# TermWylPomp1_cpu.net
KiCad netlist of a schematic drawn in Altium Designer
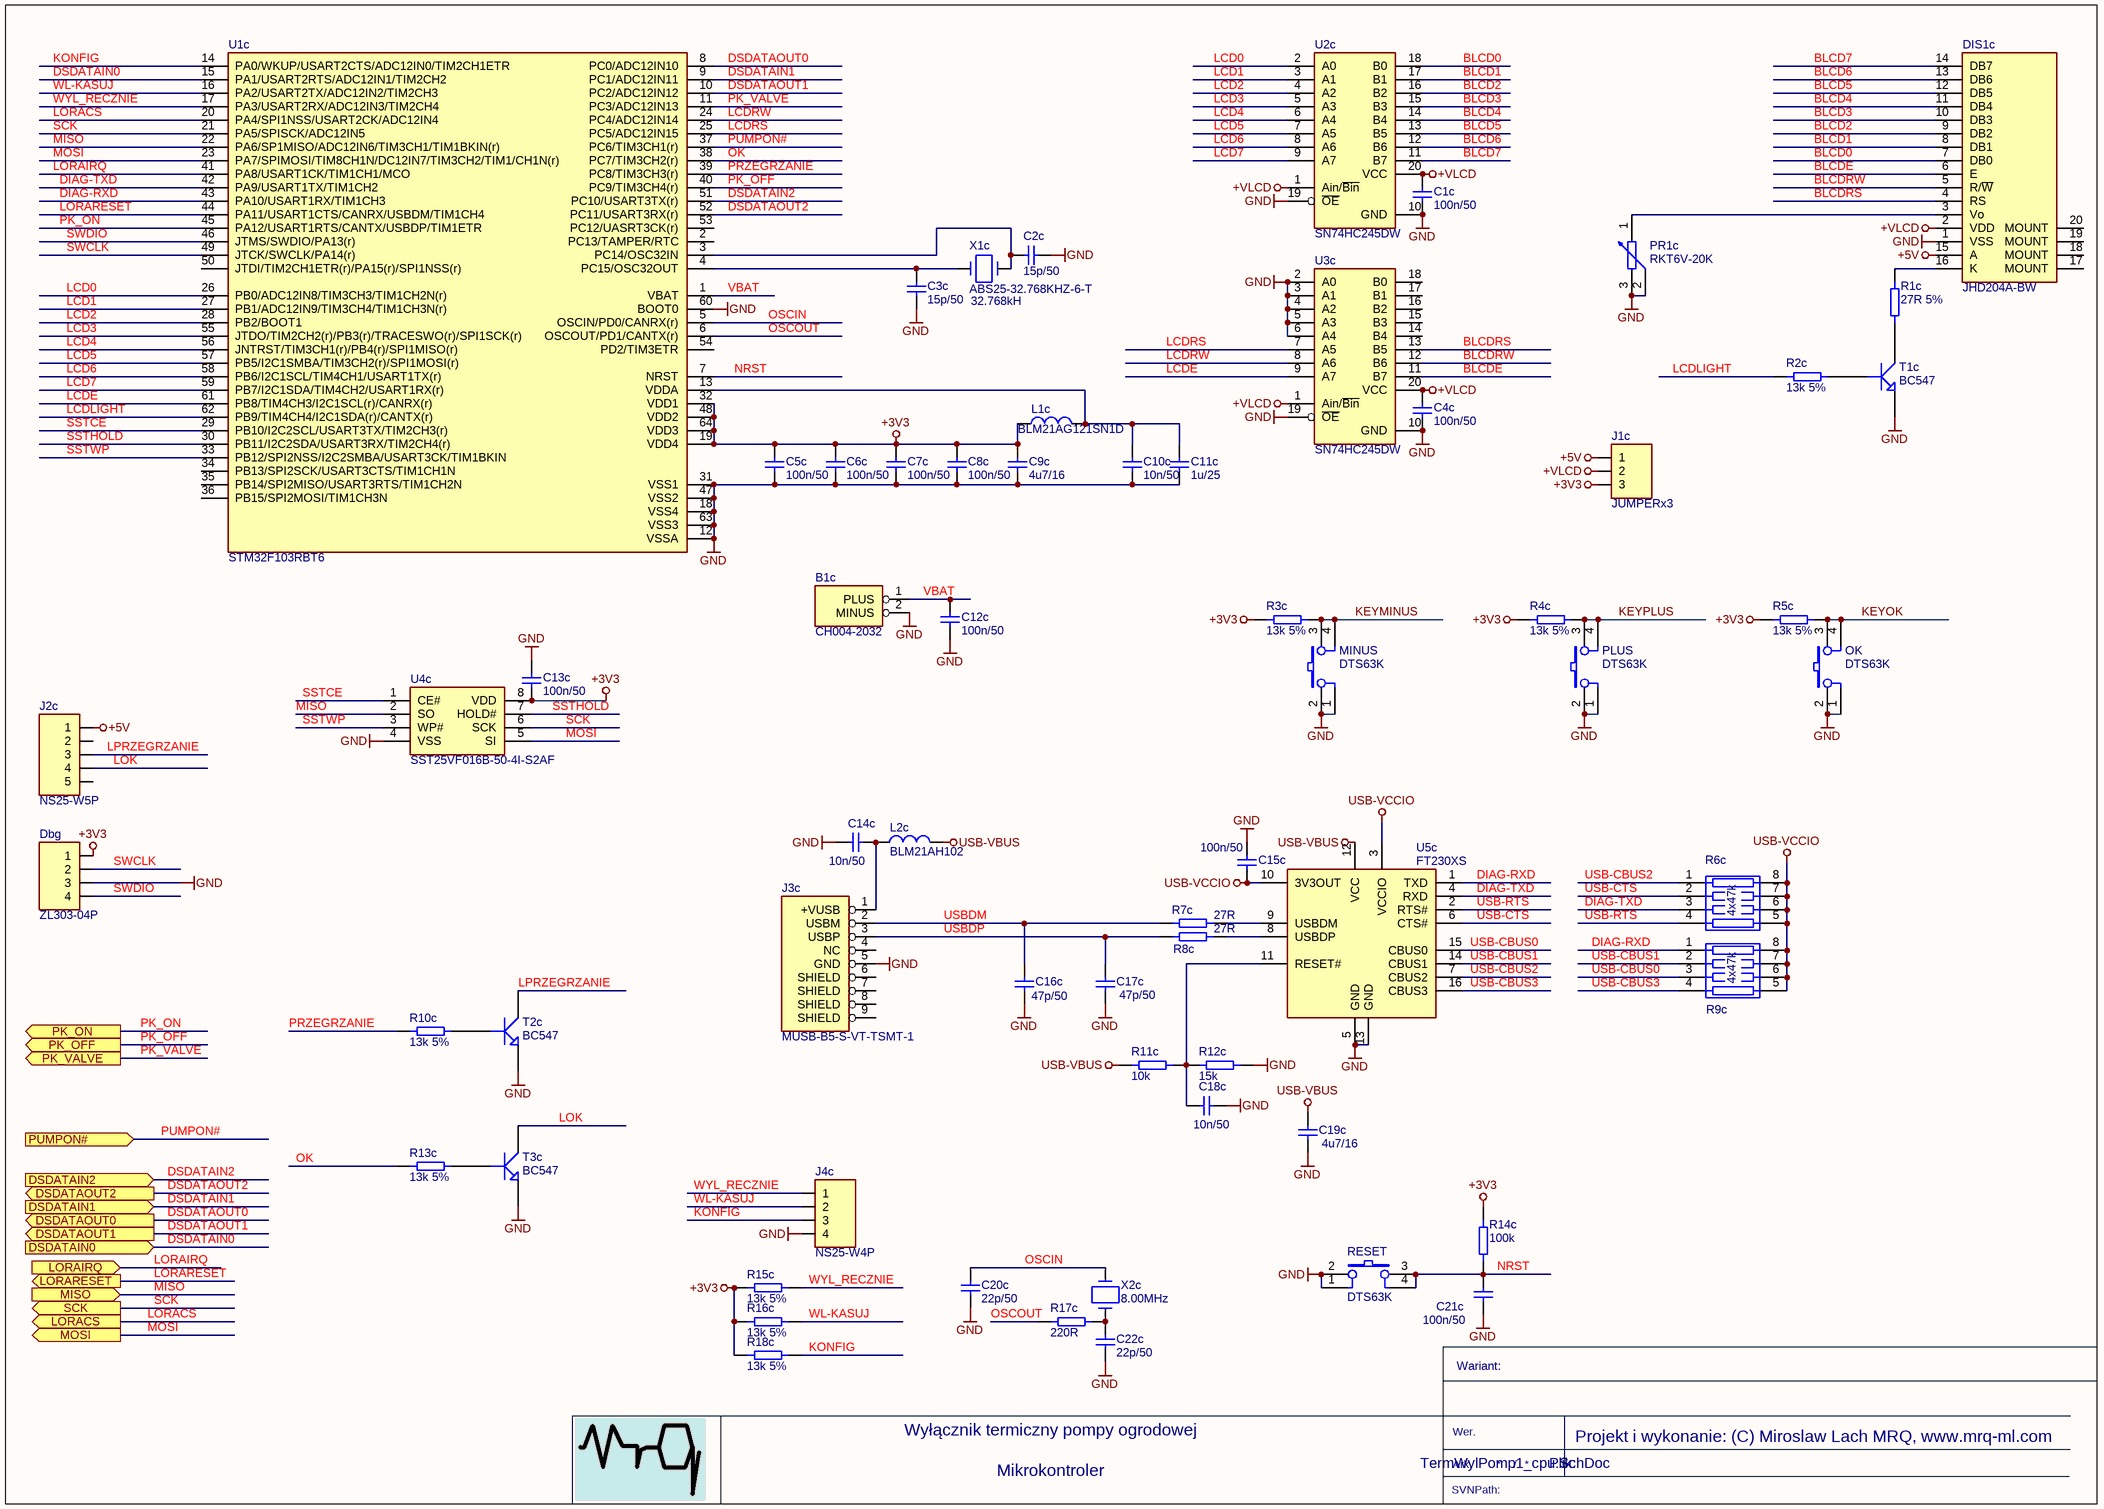
[diagram p0: TermWylPomp1_cpu.SchDoc]

(export (version "E")
  (design (tool "Eeschema 10.0.6"))
  (components
    (comp (ref "B1c")
      (value "CH004-2032")
      (footprint "CH004-2032")
      (libsource (lib "PartsMySQL") (part "BATTSOCK"))
    )
    (comp (ref "C1c") (value "100n/50") (footprint "0805") (libsource (lib "PartsMySQL") (part "C")))
    (comp (ref "C2c") (value "15p/50") (footprint "0603-IPC") (libsource (lib "PartsMySQL") (part "C")))
    (comp (ref "C3c") (value "15p/50") (footprint "0603-IPC") (libsource (lib "PartsMySQL") (part "C")))
    (comp (ref "C4c") (value "100n/50") (footprint "0805") (libsource (lib "PartsMySQL") (part "C")))
    (comp (ref "C5c") (value "100n/50") (footprint "0805") (libsource (lib "PartsMySQL") (part "C")))
    (comp (ref "C6c") (value "100n/50") (footprint "0805") (libsource (lib "PartsMySQL") (part "C")))
    (comp (ref "C7c") (value "100n/50") (footprint "0805") (libsource (lib "PartsMySQL") (part "C")))
    (comp (ref "C8c") (value "100n/50") (footprint "0805") (libsource (lib "PartsMySQL") (part "C")))
    (comp (ref "C9c") (value "4u7/16") (footprint "0805") (libsource (lib "PartsMySQL") (part "C")))
    (comp (ref "C10c") (value "10n/50") (footprint "0805") (libsource (lib "PartsMySQL") (part "C")))
    (comp (ref "C11c") (value "1u/25") (footprint "0805") (libsource (lib "PartsMySQL") (part "C")))
    (comp (ref "C12c") (value "100n/50") (footprint "0805") (libsource (lib "PartsMySQL") (part "C")))
    (comp (ref "C13c") (value "100n/50") (footprint "0805") (libsource (lib "PartsMySQL") (part "C")))
    (comp (ref "C14c") (value "10n/50") (footprint "0805") (libsource (lib "PartsMySQL") (part "C")))
    (comp (ref "C15c") (value "100n/50") (footprint "0805") (libsource (lib "PartsMySQL") (part "C")))
    (comp (ref "C16c") (value "47p/50") (footprint "0603-IPC") (libsource (lib "PartsMySQL") (part "C")))
    (comp (ref "C17c") (value "47p/50") (footprint "0603-IPC") (libsource (lib "PartsMySQL") (part "C")))
    (comp (ref "C18c") (value "10n/50") (footprint "0805") (libsource (lib "PartsMySQL") (part "C")))
    (comp (ref "C19c") (value "4u7/16") (footprint "0805") (libsource (lib "PartsMySQL") (part "C")))
    (comp (ref "C20c") (value "22p/50") (footprint "0805") (libsource (lib "PartsMySQL") (part "C")))
    (comp (ref "C21c") (value "100n/50") (footprint "0805") (libsource (lib "PartsMySQL") (part "C")))
    (comp (ref "C22c") (value "22p/50") (footprint "0805") (libsource (lib "PartsMySQL") (part "C")))
    (comp (ref "Dbg") (value "ZL303-04P") (footprint "PLMS4S") (libsource (lib "") (part "HEADER4_1")))
    (comp (ref "DIS1c")
      (value "JHD204A-BW")
      (footprint "JHD204A")
      (libsource (lib "PartsMySQL") (part "LCM2002LED"))
    )
    (comp (ref "J1c")
      (value "JUMPERx3")
      (footprint "3SIP100")
      (libsource (lib "PartsMySQL") (part "HEADER3"))
    )
    (comp (ref "J2c") (value "NS25-W5P") (footprint "WF05S") (libsource (lib "PartsMySQL") (part "HEADER5")))
    (comp (ref "J3c")
      (value "MUSB-B5-S-VT-TSMT-1")
      (footprint "MUSB-B5-S-VT-TSMT1")
      (libsource (lib "PartsMySQL") (part "MUSB-B5-S-VT-TSMT1"))
    )
    (comp (ref "J4c") (value "NS25-W4P") (footprint "WF04S") (libsource (lib "PartsMySQL") (part "HEADER4")))
    (comp (ref "L1c")
      (value "BLM21AG121SN1D")
      (footprint "0805")
      (libsource (lib "PartsMySQL") (part "INDUCTOR"))
    )
    (comp (ref "L2c")
      (value "BLM21AH102")
      (footprint "0805")
      (libsource (lib "PartsMySQL") (part "INDUCTOR"))
    )
    (comp (ref "MINUS") (value "DTS63K") (footprint "DTS63K") (libsource (lib "PartsMySQL") (part "SWPUSH")))
    (comp (ref "OK") (value "DTS63K") (footprint "DTS63K") (libsource (lib "PartsMySQL") (part "SWPUSH")))
    (comp (ref "PLUS") (value "DTS63K") (footprint "DTS63K") (libsource (lib "PartsMySQL") (part "SWPUSH")))
    (comp (ref "PR1c") (value "RKT6V-20K") (footprint "RKT6V") (libsource (lib "PartsMySQL") (part "RV2")))
    (comp (ref "R1c") (value "27R 5%") (footprint "R402510") (libsource (lib "PartsMySQL") (part "R")))
    (comp (ref "R2c") (value "13k 5%") (footprint "R402510") (libsource (lib "PartsMySQL") (part "R")))
    (comp (ref "R3c") (value "13k 5%") (footprint "R402510") (libsource (lib "PartsMySQL") (part "R")))
    (comp (ref "R4c") (value "13k 5%") (footprint "R402510") (libsource (lib "PartsMySQL") (part "R")))
    (comp (ref "R5c") (value "13k 5%") (footprint "R402510") (libsource (lib "PartsMySQL") (part "R")))
    (comp (ref "R6c") (value "4x47k") (footprint "1206RP") (libsource (lib "PartsMySQL") (part "DR1206")))
    (comp (ref "R7c") (value "27R") (footprint "0603R") (libsource (lib "PartsMySQL") (part "R")))
    (comp (ref "R8c") (value "27R") (footprint "0603R") (libsource (lib "PartsMySQL") (part "R")))
    (comp (ref "R9c") (value "4x47k") (footprint "1206RP") (libsource (lib "PartsMySQL") (part "DR1206")))
    (comp (ref "R10c") (value "13k 5%") (footprint "R402510") (libsource (lib "PartsMySQL") (part "R")))
    (comp (ref "R11c") (value "10k") (footprint "0805R") (libsource (lib "PartsMySQL") (part "R")))
    (comp (ref "R12c") (value "15k") (footprint "0805R") (libsource (lib "PartsMySQL") (part "R")))
    (comp (ref "R13c") (value "13k 5%") (footprint "R402510") (libsource (lib "PartsMySQL") (part "R")))
    (comp (ref "R14c") (value "100k") (footprint "R402510") (libsource (lib "PartsMySQL") (part "R")))
    (comp (ref "R15c") (value "13k 5%") (footprint "R402510") (libsource (lib "PartsMySQL") (part "R")))
    (comp (ref "R16c") (value "13k 5%") (footprint "R402510") (libsource (lib "PartsMySQL") (part "R")))
    (comp (ref "R17c") (value "220R") (footprint "0805R") (libsource (lib "PartsMySQL") (part "R")))
    (comp (ref "R18c") (value "13k 5%") (footprint "R402510") (libsource (lib "PartsMySQL") (part "R")))
    (comp (ref "RESET") (value "DTS63K") (footprint "DTS63K") (libsource (lib "PartsMySQL") (part "SWPUSH")))
    (comp (ref "T1c") (value "BC547") (footprint "CE35V4") (libsource (lib "PartsMySQL") (part "NPN_CE35V4")))
    (comp (ref "T2c") (value "BC547") (footprint "CE35V4") (libsource (lib "PartsMySQL") (part "NPN_CE35V4")))
    (comp (ref "T3c") (value "BC547") (footprint "CE35V4") (libsource (lib "PartsMySQL") (part "NPN_CE35V4")))
    (comp (ref "U1c")
      (value "STM32F103RBT6")
      (footprint "MS-026BCD")
      (libsource (lib "PartsMySQL") (part "STM32F103RBT6"))
    )
    (comp (ref "U2c")
      (value "SN74HC245DW")
      (footprint "20SOIC300")
      (libsource (lib "PartsMySQL") (part "74245"))
    )
    (comp (ref "U3c")
      (value "SN74HC245DW")
      (footprint "20SOIC300")
      (libsource (lib "PartsMySQL") (part "74245"))
    )
    (comp (ref "U4c")
      (value "SST25VF016B-50-4I-S2AF")
      (footprint "8SOIC200")
      (libsource (lib "PartsMySQL") (part "SST25VF016B"))
    )
    (comp (ref "U5c")
      (value "FT230XS")
      (footprint "MO-137AB")
      (libsource (lib "PartsMySQL") (part "FT230XS"))
    )
    (comp (ref "X1c")
      (value "ABS25-32.768KHZ-6-T")
      (footprint "ABS25CRYSTAL")
      (fields (field (name "FREQ") "32.768kH"))
      (libsource (lib "PartsMySQL") (part "CRYSTAL"))
    )
    (comp (ref "X2c") (value "8.00MHz") (footprint "HC49SMP") (libsource (lib "PartsMySQL") (part "CRYSTAL")))
  )
  (nets
    (net (code "1") (name "+3V3") (class "Default")
      (node (ref "C13c") (pin "1") (pinfunction "1_1") (pintype "passive"))
      (node (ref "C5c") (pin "1") (pinfunction "1_1") (pintype "passive"))
      (node (ref "C6c") (pin "1") (pinfunction "1_1") (pintype "passive"))
      (node (ref "C7c") (pin "1") (pinfunction "1_1") (pintype "passive"))
      (node (ref "C8c") (pin "1") (pinfunction "1_1") (pintype "passive"))
      (node (ref "C9c") (pin "1") (pinfunction "1_1") (pintype "passive"))
      (node (ref "Dbg") (pin "1") (pinfunction "1_1") (pintype "passive"))
      (node (ref "J1c") (pin "3") (pinfunction "3_3") (pintype "passive"))
      (node (ref "L1c") (pin "1") (pinfunction "1_1") (pintype "passive"))
      (node (ref "R14c") (pin "1") (pinfunction "1_1") (pintype "passive"))
      (node (ref "R15c") (pin "1") (pinfunction "1_1") (pintype "passive"))
      (node (ref "R16c") (pin "2") (pinfunction "2_2") (pintype "passive"))
      (node (ref "R18c") (pin "1") (pinfunction "1_1") (pintype "passive"))
      (node (ref "R3c") (pin "1") (pinfunction "1_1") (pintype "passive"))
      (node (ref "R4c") (pin "1") (pinfunction "1_1") (pintype "passive"))
      (node (ref "R5c") (pin "1") (pinfunction "1_1") (pintype "passive"))
      (node (ref "U1c") (pin "19") (pinfunction "VDD4_19") (pintype "passive"))
      (node (ref "U1c") (pin "32") (pinfunction "VDD1_32") (pintype "passive"))
      (node (ref "U1c") (pin "48") (pinfunction "VDD2_48") (pintype "passive"))
      (node (ref "U1c") (pin "64") (pinfunction "VDD3_64") (pintype "passive"))
      (node (ref "U4c") (pin "8") (pinfunction "VDD_8") (pintype "passive"))
    )
    (net (code "2") (name "+5V") (class "Default")
      (node (ref "DIS1c") (pin "15") (pinfunction "A_15") (pintype "passive"))
      (node (ref "J1c") (pin "1") (pinfunction "1_1") (pintype "passive"))
      (node (ref "J2c") (pin "1") (pinfunction "1_1") (pintype "passive"))
    )
    (net (code "3") (name "+VLCD") (class "Default")
      (node (ref "C1c") (pin "1") (pinfunction "1_1") (pintype "passive"))
      (node (ref "C4c") (pin "1") (pinfunction "1_1") (pintype "passive"))
      (node (ref "DIS1c") (pin "2") (pinfunction "VDD_2") (pintype "passive"))
      (node (ref "J1c") (pin "2") (pinfunction "2_2") (pintype "passive"))
      (node (ref "U2c") (pin "1") (pinfunction "Ain/~{Bin}_1") (pintype "passive"))
      (node (ref "U2c") (pin "20") (pinfunction "VCC_20") (pintype "power_in"))
      (node (ref "U3c") (pin "1") (pinfunction "Ain/~{Bin}_1") (pintype "passive"))
      (node (ref "U3c") (pin "20") (pinfunction "VCC_20") (pintype "power_in"))
    )
    (net (code "4") (name "/BLCD0") (class "Default")
      (node (ref "DIS1c") (pin "7") (pinfunction "DB0_7") (pintype "passive"))
      (node (ref "U2c") (pin "18") (pinfunction "B0_18") (pintype "passive"))
    )
    (net (code "5") (name "/BLCD1") (class "Default")
      (node (ref "DIS1c") (pin "8") (pinfunction "DB1_8") (pintype "passive"))
      (node (ref "U2c") (pin "17") (pinfunction "B1_17") (pintype "passive"))
    )
    (net (code "6") (name "/BLCD2") (class "Default")
      (node (ref "DIS1c") (pin "9") (pinfunction "DB2_9") (pintype "passive"))
      (node (ref "U2c") (pin "16") (pinfunction "B2_16") (pintype "passive"))
    )
    (net (code "7") (name "/BLCD3") (class "Default")
      (node (ref "DIS1c") (pin "10") (pinfunction "DB3_10") (pintype "passive"))
      (node (ref "U2c") (pin "15") (pinfunction "B3_15") (pintype "passive"))
    )
    (net (code "8") (name "/BLCD4") (class "Default")
      (node (ref "DIS1c") (pin "11") (pinfunction "DB4_11") (pintype "passive"))
      (node (ref "U2c") (pin "14") (pinfunction "B4_14") (pintype "passive"))
    )
    (net (code "9") (name "/BLCD5") (class "Default")
      (node (ref "DIS1c") (pin "12") (pinfunction "DB5_12") (pintype "passive"))
      (node (ref "U2c") (pin "13") (pinfunction "B5_13") (pintype "passive"))
    )
    (net (code "10") (name "/BLCD6") (class "Default")
      (node (ref "DIS1c") (pin "13") (pinfunction "DB6_13") (pintype "passive"))
      (node (ref "U2c") (pin "12") (pinfunction "B6_12") (pintype "passive"))
    )
    (net (code "11") (name "/BLCD7") (class "Default")
      (node (ref "DIS1c") (pin "14") (pinfunction "DB7_14") (pintype "passive"))
      (node (ref "U2c") (pin "11") (pinfunction "B7_11") (pintype "passive"))
    )
    (net (code "12") (name "/BLCDE") (class "Default")
      (node (ref "DIS1c") (pin "6") (pinfunction "E_6") (pintype "passive"))
      (node (ref "U3c") (pin "11") (pinfunction "B7_11") (pintype "passive"))
    )
    (net (code "13") (name "/BLCDRS") (class "Default")
      (node (ref "DIS1c") (pin "4") (pinfunction "RS_4") (pintype "passive"))
      (node (ref "U3c") (pin "13") (pinfunction "B5_13") (pintype "passive"))
    )
    (net (code "14") (name "/BLCDRW") (class "Default")
      (node (ref "DIS1c") (pin "5") (pinfunction "R/~{W}_5") (pintype "passive"))
      (node (ref "U3c") (pin "12") (pinfunction "B6_12") (pintype "passive"))
    )
    (net (code "15") (name "/DIAG-RXD") (class "Default")
      (node (ref "R9c") (pin "1") (pinfunction "R1_1") (pintype "passive"))
      (node (ref "U1c") (pin "43") (pinfunction "PA10/USART1RX/TIM1CH3_43") (pintype "passive"))
      (node (ref "U5c") (pin "1") (pinfunction "TXD_1") (pintype "passive"))
    )
    (net (code "16") (name "/DIAG-TXD") (class "Default")
      (node (ref "R6c") (pin "3") (pinfunction "R3_3") (pintype "passive"))
      (node (ref "U1c") (pin "42") (pinfunction "PA9/USART1TX/TIM1CH2_42") (pintype "passive"))
      (node (ref "U5c") (pin "4") (pinfunction "RXD_4") (pintype "passive"))
    )
    (net (code "17") (name "/DSDATAIN0") (class "Default")
      (node (ref "U1c") (pin "15") (pinfunction "PA1/USART2RTS/ADC12IN1/TIM2CH2_15") (pintype "passive"))
    )
    (net (code "18") (name "/DSDATAIN1") (class "Default")
      (node (ref "U1c") (pin "9") (pinfunction "PC1/ADC12IN11_9") (pintype "passive"))
    )
    (net (code "19") (name "/DSDATAIN2") (class "Default")
      (node (ref "U1c") (pin "51") (pinfunction "PC10/USART3TX(r)_51") (pintype "passive"))
    )
    (net (code "20") (name "/DSDATAOUT0") (class "Default")
      (node (ref "U1c") (pin "8") (pinfunction "PC0/ADC12IN10_8") (pintype "passive"))
    )
    (net (code "21") (name "/DSDATAOUT1") (class "Default")
      (node (ref "U1c") (pin "10") (pinfunction "PC2/ADC12IN12_10") (pintype "passive"))
    )
    (net (code "22") (name "/DSDATAOUT2") (class "Default")
      (node (ref "U1c") (pin "52") (pinfunction "PC11/USART3RX(r)_52") (pintype "passive"))
    )
    (net (code "23") (name "/KEYMINUS") (class "Default")
      (node (ref "MINUS") (pin "3") (pinfunction "3_3") (pintype "passive"))
      (node (ref "MINUS") (pin "4") (pinfunction "4_4") (pintype "passive"))
      (node (ref "R3c") (pin "2") (pinfunction "2_2") (pintype "passive"))
    )
    (net (code "24") (name "/KEYOK") (class "Default")
      (node (ref "OK") (pin "3") (pinfunction "3_3") (pintype "passive"))
      (node (ref "OK") (pin "4") (pinfunction "4_4") (pintype "passive"))
      (node (ref "R5c") (pin "2") (pinfunction "2_2") (pintype "passive"))
    )
    (net (code "25") (name "/KEYPLUS") (class "Default")
      (node (ref "PLUS") (pin "3") (pinfunction "3_3") (pintype "passive"))
      (node (ref "PLUS") (pin "4") (pinfunction "4_4") (pintype "passive"))
      (node (ref "R4c") (pin "2") (pinfunction "2_2") (pintype "passive"))
    )
    (net (code "26") (name "/KONFIG") (class "Default")
      (node (ref "J4c") (pin "3") (pinfunction "3_3") (pintype "passive"))
      (node (ref "R18c") (pin "2") (pinfunction "2_2") (pintype "passive"))
      (node (ref "U1c") (pin "14") (pinfunction "PA0/WKUP/USART2CTS/ADC12IN0/TIM2CH1ETR_14") (pintype "passive"))
    )
    (net (code "27") (name "/LCD0") (class "Default")
      (node (ref "U1c") (pin "26") (pinfunction "PB0/ADC12IN8/TIM3CH3/TIM1CH2N(r)_26") (pintype "passive"))
      (node (ref "U2c") (pin "2") (pinfunction "A0_2") (pintype "passive"))
    )
    (net (code "28") (name "/LCD1") (class "Default")
      (node (ref "U1c") (pin "27") (pinfunction "PB1/ADC12IN9/TIM3CH4/TIM1CH3N(r)_27") (pintype "passive"))
      (node (ref "U2c") (pin "3") (pinfunction "A1_3") (pintype "passive"))
    )
    (net (code "29") (name "/LCD2") (class "Default")
      (node (ref "U1c") (pin "28") (pinfunction "PB2/BOOT1_28") (pintype "passive"))
      (node (ref "U2c") (pin "4") (pinfunction "A2_4") (pintype "passive"))
    )
    (net (code "30") (name "/LCD3") (class "Default")
      (node (ref "U1c") (pin "55") (pinfunction "JTDO/TIM2CH2(r)/PB3(r)/TRACESWO(r)/SPI1SCK(r)_55") (pintype "passive"))
      (node (ref "U2c") (pin "5") (pinfunction "A3_5") (pintype "passive"))
    )
    (net (code "31") (name "/LCD4") (class "Default")
      (node (ref "U1c") (pin "56") (pinfunction "JNTRST/TIM3CH1(r)/PB4(r)/SPI1MISO(r)_56") (pintype "passive"))
      (node (ref "U2c") (pin "6") (pinfunction "A4_6") (pintype "passive"))
    )
    (net (code "32") (name "/LCD5") (class "Default")
      (node (ref "U1c") (pin "57") (pinfunction "PB5/I2C1SMBA/TIM3CH2(r)/SPI1MOSI(r)_57") (pintype "passive"))
      (node (ref "U2c") (pin "7") (pinfunction "A5_7") (pintype "passive"))
    )
    (net (code "33") (name "/LCD6") (class "Default")
      (node (ref "U1c") (pin "58") (pinfunction "PB6/I2C1SCL/TIM4CH1/USART1TX(r)_58") (pintype "passive"))
      (node (ref "U2c") (pin "8") (pinfunction "A6_8") (pintype "passive"))
    )
    (net (code "34") (name "/LCD7") (class "Default")
      (node (ref "U1c") (pin "59") (pinfunction "PB7/I2C1SDA/TIM4CH2/USART1RX(r)_59") (pintype "passive"))
      (node (ref "U2c") (pin "9") (pinfunction "A7_9") (pintype "passive"))
    )
    (net (code "35") (name "/LCDE") (class "Default")
      (node (ref "U1c") (pin "61") (pinfunction "PB8/TIM4CH3/I2C1SCL(r)/CANRX(r)_61") (pintype "passive"))
      (node (ref "U3c") (pin "9") (pinfunction "A7_9") (pintype "passive"))
    )
    (net (code "36") (name "/LCDLIGHT") (class "Default")
      (node (ref "R2c") (pin "1") (pinfunction "1_1") (pintype "passive"))
      (node (ref "U1c") (pin "62") (pinfunction "PB9/TIM4CH4/I2C1SDA(r)/CANTX(r)_62") (pintype "passive"))
    )
    (net (code "37") (name "/LCDRS") (class "Default")
      (node (ref "U1c") (pin "25") (pinfunction "PC5/ADC12IN15_25") (pintype "passive"))
      (node (ref "U3c") (pin "7") (pinfunction "A5_7") (pintype "passive"))
    )
    (net (code "38") (name "/LCDRW") (class "Default")
      (node (ref "U1c") (pin "24") (pinfunction "PC4/ADC12IN14_24") (pintype "passive"))
      (node (ref "U3c") (pin "8") (pinfunction "A6_8") (pintype "passive"))
    )
    (net (code "39") (name "/LOK") (class "Default")
      (node (ref "J2c") (pin "4") (pinfunction "4_4") (pintype "passive"))
      (node (ref "T3c") (pin "COLL") (pinfunction "COLL_COLL") (pintype "passive"))
    )
    (net (code "40") (name "/LORACS") (class "Default")
      (node (ref "U1c") (pin "20") (pinfunction "PA4/SPI1NSS/USART2CK/ADC12IN4_20") (pintype "passive"))
    )
    (net (code "41") (name "/LORAIRQ") (class "Default")
      (node (ref "U1c") (pin "41") (pinfunction "PA8/USART1CK/TIM1CH1/MCO_41") (pintype "passive"))
    )
    (net (code "42") (name "/LORARESET") (class "Default")
      (node (ref "U1c") (pin "44") (pinfunction "PA11/USART1CTS/CANRX/USBDM/TIM1CH4_44") (pintype "passive"))
    )
    (net (code "43") (name "/LPRZEGRZANIE") (class "Default")
      (node (ref "J2c") (pin "3") (pinfunction "3_3") (pintype "passive"))
      (node (ref "T2c") (pin "COLL") (pinfunction "COLL_COLL") (pintype "passive"))
    )
    (net (code "44") (name "/MISO") (class "Default")
      (node (ref "U1c") (pin "22") (pinfunction "PA6/SP1MISO/ADC12IN6/TIM3CH1/TIM1BKIN(r)_22") (pintype "passive"))
      (node (ref "U4c") (pin "2") (pinfunction "SO_2") (pintype "passive"))
    )
    (net (code "45") (name "/MOSI") (class "Default")
      (node (ref "U1c") (pin "23") (pinfunction "PA7/SPIMOSI/TIM8CH1N/DC12IN7/TIM3CH2/TIM1/CH1N(r)_23") (pintype "passive"))
      (node (ref "U4c") (pin "5") (pinfunction "SI_5") (pintype "passive"))
    )
    (net (code "46") (name "/NRST") (class "Default")
      (node (ref "C21c") (pin "1") (pinfunction "1_1") (pintype "passive"))
      (node (ref "R14c") (pin "2") (pinfunction "2_2") (pintype "passive"))
      (node (ref "RESET") (pin "3") (pinfunction "3_3") (pintype "passive"))
      (node (ref "RESET") (pin "4") (pinfunction "4_4") (pintype "passive"))
      (node (ref "U1c") (pin "7") (pinfunction "NRST_7") (pintype "passive"))
    )
    (net (code "47") (name "/OK") (class "Default")
      (node (ref "R13c") (pin "1") (pinfunction "1_1") (pintype "passive"))
      (node (ref "U1c") (pin "38") (pinfunction "PC7/TIM3CH2(r)_38") (pintype "passive"))
    )
    (net (code "48") (name "/OSCIN") (class "Default")
      (node (ref "C20c") (pin "2") (pinfunction "2_2") (pintype "passive"))
      (node (ref "U1c") (pin "5") (pinfunction "OSCIN/PD0/CANRX(r)_5") (pintype "passive"))
      (node (ref "X2c") (pin "2") (pinfunction "2_2") (pintype "passive"))
    )
    (net (code "49") (name "/OSCOUT") (class "Default")
      (node (ref "R17c") (pin "1") (pinfunction "1_1") (pintype "passive"))
      (node (ref "U1c") (pin "6") (pinfunction "OSCOUT/PD1/CANTX(r)_6") (pintype "passive"))
    )
    (net (code "50") (name "/PK_OFF") (class "Default")
      (node (ref "U1c") (pin "40") (pinfunction "PC9/TIM3CH4(r)_40") (pintype "passive"))
    )
    (net (code "51") (name "/PK_ON") (class "Default")
      (node (ref "U1c") (pin "45") (pinfunction "PA12/USART1RTS/CANTX/USBDP/TIM1ETR_45") (pintype "passive"))
    )
    (net (code "52") (name "/PK_VALVE") (class "Default")
      (node (ref "U1c") (pin "11") (pinfunction "PC3/ADC12IN13_11") (pintype "passive"))
    )
    (net (code "53") (name "/PRZEGRZANIE") (class "Default")
      (node (ref "R10c") (pin "1") (pinfunction "1_1") (pintype "passive"))
      (node (ref "U1c") (pin "39") (pinfunction "PC8/TIM3CH3(r)_39") (pintype "passive"))
    )
    (net (code "54") (name "/PUMPON#") (class "Default")
      (node (ref "U1c") (pin "37") (pinfunction "PC6/TIM3CH1(r)_37") (pintype "passive"))
    )
    (net (code "55") (name "/SCK") (class "Default")
      (node (ref "U1c") (pin "21") (pinfunction "PA5/SPISCK/ADC12IN5_21") (pintype "passive"))
      (node (ref "U4c") (pin "6") (pinfunction "SCK_6") (pintype "passive"))
    )
    (net (code "56") (name "/SSTCE") (class "Default")
      (node (ref "U1c") (pin "29") (pinfunction "PB10/I2C2SCL/USART3TX/TIM2CH3(r)_29") (pintype "passive"))
      (node (ref "U4c") (pin "1") (pinfunction "CE#_1") (pintype "passive"))
    )
    (net (code "57") (name "/SSTHOLD") (class "Default")
      (node (ref "U1c") (pin "30") (pinfunction "PB11/I2C2SDA/USART3RX/TIM2CH4(r)_30") (pintype "passive"))
      (node (ref "U4c") (pin "7") (pinfunction "HOLD#_7") (pintype "passive"))
    )
    (net (code "58") (name "/SSTWP") (class "Default")
      (node (ref "U1c") (pin "33") (pinfunction "PB12/SPI2NSS/I2C2SMBA/USART3CK/TIM1BKIN_33") (pintype "passive"))
      (node (ref "U4c") (pin "3") (pinfunction "WP#_3") (pintype "passive"))
    )
    (net (code "59") (name "/SWCLK") (class "Default")
      (node (ref "Dbg") (pin "2") (pinfunction "2_2") (pintype "passive"))
      (node (ref "U1c") (pin "49") (pinfunction "JTCK/SWCLK/PA14(r)_49") (pintype "passive"))
    )
    (net (code "60") (name "/SWDIO") (class "Default")
      (node (ref "Dbg") (pin "4") (pinfunction "4_4") (pintype "passive"))
      (node (ref "U1c") (pin "46") (pinfunction "JTMS/SWDIO/PA13(r)_46") (pintype "passive"))
    )
    (net (code "61") (name "/USB-CBUS0") (class "Default")
      (node (ref "R9c") (pin "3") (pinfunction "R3_3") (pintype "passive"))
      (node (ref "U5c") (pin "15") (pinfunction "CBUS0_15") (pintype "passive"))
    )
    (net (code "62") (name "/USB-CBUS1") (class "Default")
      (node (ref "R9c") (pin "2") (pinfunction "R2_2") (pintype "passive"))
      (node (ref "U5c") (pin "14") (pinfunction "CBUS1_14") (pintype "passive"))
    )
    (net (code "63") (name "/USB-CBUS2") (class "Default")
      (node (ref "R6c") (pin "1") (pinfunction "R1_1") (pintype "passive"))
      (node (ref "U5c") (pin "7") (pinfunction "CBUS2_7") (pintype "passive"))
    )
    (net (code "64") (name "/USB-CBUS3") (class "Default")
      (node (ref "R9c") (pin "4") (pinfunction "R4_4") (pintype "passive"))
      (node (ref "U5c") (pin "16") (pinfunction "CBUS3_16") (pintype "passive"))
    )
    (net (code "65") (name "/USB-CTS") (class "Default")
      (node (ref "R6c") (pin "2") (pinfunction "R2_2") (pintype "passive"))
      (node (ref "U5c") (pin "6") (pinfunction "CTS#_6") (pintype "passive"))
    )
    (net (code "66") (name "/USB-RTS") (class "Default")
      (node (ref "R6c") (pin "4") (pinfunction "R4_4") (pintype "passive"))
      (node (ref "U5c") (pin "2") (pinfunction "RTS#_2") (pintype "passive"))
    )
    (net (code "67") (name "/USBDM") (class "Default")
      (node (ref "C16c") (pin "1") (pinfunction "1_1") (pintype "passive"))
      (node (ref "J3c") (pin "2") (pinfunction "USBM_2") (pintype "passive"))
      (node (ref "R7c") (pin "1") (pinfunction "1_1") (pintype "passive"))
    )
    (net (code "68") (name "/USBDP") (class "Default")
      (node (ref "C17c") (pin "1") (pinfunction "1_1") (pintype "passive"))
      (node (ref "J3c") (pin "3") (pinfunction "USBP_3") (pintype "passive"))
      (node (ref "R8c") (pin "1") (pinfunction "1_1") (pintype "passive"))
    )
    (net (code "69") (name "/VBAT") (class "Default")
      (node (ref "B1c") (pin "1") (pinfunction "PLUS_1") (pintype "passive"))
      (node (ref "C12c") (pin "1") (pinfunction "1_1") (pintype "passive"))
      (node (ref "U1c") (pin "1") (pinfunction "VBAT_1") (pintype "passive"))
    )
    (net (code "70") (name "/WL-KASUJ") (class "Default")
      (node (ref "J4c") (pin "2") (pinfunction "2_2") (pintype "passive"))
      (node (ref "R16c") (pin "1") (pinfunction "1_1") (pintype "passive"))
      (node (ref "U1c") (pin "16") (pinfunction "PA2/USART2TX/ADC12IN2/TIM2CH3_16") (pintype "passive"))
    )
    (net (code "71") (name "/WYL_RECZNIE") (class "Default")
      (node (ref "J4c") (pin "1") (pinfunction "1_1") (pintype "passive"))
      (node (ref "R15c") (pin "2") (pinfunction "2_2") (pintype "passive"))
      (node (ref "U1c") (pin "17") (pinfunction "PA3/USART2RX/ADC12IN3/TIM2CH4_17") (pintype "passive"))
    )
    (net (code "72") (name "GND") (class "Default")
      (node (ref "B1c") (pin "2") (pinfunction "MINUS_2") (pintype "passive"))
      (node (ref "C10c") (pin "2") (pinfunction "2_2") (pintype "passive"))
      (node (ref "C11c") (pin "2") (pinfunction "2_2") (pintype "passive"))
      (node (ref "C12c") (pin "2") (pinfunction "2_2") (pintype "passive"))
      (node (ref "C13c") (pin "2") (pinfunction "2_2") (pintype "passive"))
      (node (ref "C14c") (pin "1") (pinfunction "1_1") (pintype "passive"))
      (node (ref "C15c") (pin "1") (pinfunction "1_1") (pintype "passive"))
      (node (ref "C16c") (pin "2") (pinfunction "2_2") (pintype "passive"))
      (node (ref "C17c") (pin "2") (pinfunction "2_2") (pintype "passive"))
      (node (ref "C18c") (pin "1") (pinfunction "1_1") (pintype "passive"))
      (node (ref "C19c") (pin "2") (pinfunction "2_2") (pintype "passive"))
      (node (ref "C1c") (pin "2") (pinfunction "2_2") (pintype "passive"))
      (node (ref "C20c") (pin "1") (pinfunction "1_1") (pintype "passive"))
      (node (ref "C21c") (pin "2") (pinfunction "2_2") (pintype "passive"))
      (node (ref "C22c") (pin "1") (pinfunction "1_1") (pintype "passive"))
      (node (ref "C2c") (pin "1") (pinfunction "1_1") (pintype "passive"))
      (node (ref "C3c") (pin "1") (pinfunction "1_1") (pintype "passive"))
      (node (ref "C4c") (pin "2") (pinfunction "2_2") (pintype "passive"))
      (node (ref "C5c") (pin "2") (pinfunction "2_2") (pintype "passive"))
      (node (ref "C6c") (pin "2") (pinfunction "2_2") (pintype "passive"))
      (node (ref "C7c") (pin "2") (pinfunction "2_2") (pintype "passive"))
      (node (ref "C8c") (pin "2") (pinfunction "2_2") (pintype "passive"))
      (node (ref "C9c") (pin "2") (pinfunction "2_2") (pintype "passive"))
      (node (ref "DIS1c") (pin "1") (pinfunction "VSS_1") (pintype "passive"))
      (node (ref "Dbg") (pin "3") (pinfunction "3_3") (pintype "passive"))
      (node (ref "J3c") (pin "5") (pinfunction "GND_5") (pintype "passive"))
      (node (ref "J4c") (pin "4") (pinfunction "4_4") (pintype "passive"))
      (node (ref "MINUS") (pin "1") (pinfunction "1_1") (pintype "passive"))
      (node (ref "MINUS") (pin "2") (pinfunction "2_2") (pintype "passive"))
      (node (ref "OK") (pin "1") (pinfunction "1_1") (pintype "passive"))
      (node (ref "OK") (pin "2") (pinfunction "2_2") (pintype "passive"))
      (node (ref "PLUS") (pin "1") (pinfunction "1_1") (pintype "passive"))
      (node (ref "PLUS") (pin "2") (pinfunction "2_2") (pintype "passive"))
      (node (ref "PR1c") (pin "2") (pinfunction "2_2") (pintype "passive"))
      (node (ref "PR1c") (pin "3") (pinfunction "3_3") (pintype "passive"))
      (node (ref "R12c") (pin "2") (pinfunction "2_2") (pintype "passive"))
      (node (ref "RESET") (pin "1") (pinfunction "1_1") (pintype "passive"))
      (node (ref "RESET") (pin "2") (pinfunction "2_2") (pintype "passive"))
      (node (ref "T1c") (pin "EMIT") (pinfunction "EMIT_EMIT") (pintype "passive"))
      (node (ref "T2c") (pin "EMIT") (pinfunction "EMIT_EMIT") (pintype "passive"))
      (node (ref "T3c") (pin "EMIT") (pinfunction "EMIT_EMIT") (pintype "passive"))
      (node (ref "U1c") (pin "12") (pinfunction "VSSA_12") (pintype "passive"))
      (node (ref "U1c") (pin "18") (pinfunction "VSS4_18") (pintype "passive"))
      (node (ref "U1c") (pin "31") (pinfunction "VSS1_31") (pintype "passive"))
      (node (ref "U1c") (pin "47") (pinfunction "VSS2_47") (pintype "passive"))
      (node (ref "U1c") (pin "60") (pinfunction "BOOT0_60") (pintype "passive"))
      (node (ref "U1c") (pin "63") (pinfunction "VSS3_63") (pintype "passive"))
      (node (ref "U2c") (pin "10") (pinfunction "GND_10") (pintype "power_in"))
      (node (ref "U2c") (pin "19") (pinfunction "~{OE}_19") (pintype "passive"))
      (node (ref "U3c") (pin "10") (pinfunction "GND_10") (pintype "power_in"))
      (node (ref "U3c") (pin "19") (pinfunction "~{OE}_19") (pintype "passive"))
      (node (ref "U3c") (pin "2") (pinfunction "A0_2") (pintype "passive"))
      (node (ref "U3c") (pin "3") (pinfunction "A1_3") (pintype "passive"))
      (node (ref "U3c") (pin "4") (pinfunction "A2_4") (pintype "passive"))
      (node (ref "U3c") (pin "5") (pinfunction "A3_5") (pintype "passive"))
      (node (ref "U3c") (pin "6") (pinfunction "A4_6") (pintype "passive"))
      (node (ref "U4c") (pin "4") (pinfunction "VSS_4") (pintype "passive"))
      (node (ref "U5c") (pin "13") (pinfunction "GND_13") (pintype "passive"))
      (node (ref "U5c") (pin "5") (pinfunction "GND_5") (pintype "passive"))
    )
    (net (code "73") (name "Net-(C22c-Pad2)") (class "Default")
      (node (ref "C22c") (pin "2") (pinfunction "2_2") (pintype "passive"))
      (node (ref "R17c") (pin "2") (pinfunction "2_2") (pintype "passive"))
      (node (ref "X2c") (pin "1") (pinfunction "1_1") (pintype "passive"))
    )
    (net (code "74") (name "Net-(DIS1c-K)") (class "Default")
      (node (ref "DIS1c") (pin "16") (pinfunction "K_16") (pintype "passive"))
      (node (ref "R1c") (pin "1") (pinfunction "1_1") (pintype "passive"))
    )
    (net (code "75") (name "Net-(DIS1c-Vo)") (class "Default")
      (node (ref "DIS1c") (pin "3") (pinfunction "Vo_3") (pintype "passive"))
      (node (ref "PR1c") (pin "1") (pinfunction "1_1") (pintype "passive"))
    )
    (net (code "76") (name "Net-(J3c-+VUSB)") (class "Default")
      (node (ref "C14c") (pin "2") (pinfunction "2_2") (pintype "passive"))
      (node (ref "J3c") (pin "1") (pinfunction "+VUSB_1") (pintype "passive"))
      (node (ref "L2c") (pin "1") (pinfunction "1_1") (pintype "passive"))
    )
    (net (code "77") (name "Net-(R1c-Pad2)") (class "Default")
      (node (ref "R1c") (pin "2") (pinfunction "2_2") (pintype "passive"))
      (node (ref "T1c") (pin "COLL") (pinfunction "COLL_COLL") (pintype "passive"))
    )
    (net (code "78") (name "Net-(R2c-Pad2)") (class "Default")
      (node (ref "R2c") (pin "2") (pinfunction "2_2") (pintype "passive"))
      (node (ref "T1c") (pin "BASE") (pinfunction "BASE_BASE") (pintype "passive"))
    )
    (net (code "79") (name "Net-(R10c-Pad2)") (class "Default")
      (node (ref "R10c") (pin "2") (pinfunction "2_2") (pintype "passive"))
      (node (ref "T2c") (pin "BASE") (pinfunction "BASE_BASE") (pintype "passive"))
    )
    (net (code "80") (name "Net-(R13c-Pad2)") (class "Default")
      (node (ref "R13c") (pin "2") (pinfunction "2_2") (pintype "passive"))
      (node (ref "T3c") (pin "BASE") (pinfunction "BASE_BASE") (pintype "passive"))
    )
    (net (code "81") (name "Net-(U1c-PC14{slash}OSC32IN)") (class "Default")
      (node (ref "C2c") (pin "2") (pinfunction "2_2") (pintype "passive"))
      (node (ref "U1c") (pin "3") (pinfunction "PC14/OSC32IN_3") (pintype "passive"))
      (node (ref "X1c") (pin "1") (pinfunction "1_1") (pintype "passive"))
    )
    (net (code "82") (name "Net-(U1c-PC15{slash}OSC32OUT)") (class "Default")
      (node (ref "C3c") (pin "2") (pinfunction "2_2") (pintype "passive"))
      (node (ref "U1c") (pin "4") (pinfunction "PC15/OSC32OUT_4") (pintype "passive"))
      (node (ref "X1c") (pin "2") (pinfunction "2_2") (pintype "passive"))
    )
    (net (code "83") (name "Net-(U1c-VDDA)") (class "Default")
      (node (ref "C10c") (pin "1") (pinfunction "1_1") (pintype "passive"))
      (node (ref "C11c") (pin "1") (pinfunction "1_1") (pintype "passive"))
      (node (ref "L1c") (pin "2") (pinfunction "2_2") (pintype "passive"))
      (node (ref "U1c") (pin "13") (pinfunction "VDDA_13") (pintype "passive"))
    )
    (net (code "84") (name "Net-(U5c-RESET#)") (class "Default")
      (node (ref "C18c") (pin "2") (pinfunction "2_2") (pintype "passive"))
      (node (ref "R11c") (pin "2") (pinfunction "2_2") (pintype "passive"))
      (node (ref "R12c") (pin "1") (pinfunction "1_1") (pintype "passive"))
      (node (ref "U5c") (pin "11") (pinfunction "RESET#_11") (pintype "passive"))
    )
    (net (code "85") (name "Net-(U5c-USBDM)") (class "Default")
      (node (ref "R7c") (pin "2") (pinfunction "2_2") (pintype "passive"))
      (node (ref "U5c") (pin "9") (pinfunction "USBDM_9") (pintype "passive"))
    )
    (net (code "86") (name "Net-(U5c-USBDP)") (class "Default")
      (node (ref "R8c") (pin "2") (pinfunction "2_2") (pintype "passive"))
      (node (ref "U5c") (pin "8") (pinfunction "USBDP_8") (pintype "passive"))
    )
    (net (code "87") (name "USB-VBUS") (class "Default")
      (node (ref "C19c") (pin "1") (pinfunction "1_1") (pintype "passive"))
      (node (ref "L2c") (pin "2") (pinfunction "2_2") (pintype "passive"))
      (node (ref "R11c") (pin "1") (pinfunction "1_1") (pintype "passive"))
      (node (ref "U5c") (pin "12") (pinfunction "VCC_12") (pintype "passive"))
    )
    (net (code "88") (name "USB-VCCIO") (class "Default")
      (node (ref "C15c") (pin "2") (pinfunction "2_2") (pintype "passive"))
      (node (ref "R6c") (pin "5") (pinfunction "R5_5") (pintype "passive"))
      (node (ref "R6c") (pin "6") (pinfunction "R6_6") (pintype "passive"))
      (node (ref "R6c") (pin "7") (pinfunction "R7_7") (pintype "passive"))
      (node (ref "R6c") (pin "8") (pinfunction "R8_8") (pintype "passive"))
      (node (ref "R9c") (pin "5") (pinfunction "R5_5") (pintype "passive"))
      (node (ref "R9c") (pin "6") (pinfunction "R6_6") (pintype "passive"))
      (node (ref "R9c") (pin "7") (pinfunction "R7_7") (pintype "passive"))
      (node (ref "R9c") (pin "8") (pinfunction "R8_8") (pintype "passive"))
      (node (ref "U5c") (pin "10") (pinfunction "3V3OUT_10") (pintype "passive"))
      (node (ref "U5c") (pin "3") (pinfunction "VCCIO_3") (pintype "passive"))
    )
    (net (code "89") (name "unconnected-(DIS1c-MOUNT-Pad17)") (class "Default")
      (node (ref "DIS1c") (pin "17") (pinfunction "MOUNT_17") (pintype "passive"))
    )
    (net (code "90") (name "unconnected-(DIS1c-MOUNT-Pad18)") (class "Default")
      (node (ref "DIS1c") (pin "18") (pinfunction "MOUNT_18") (pintype "passive"))
    )
    (net (code "91") (name "unconnected-(DIS1c-MOUNT-Pad19)") (class "Default")
      (node (ref "DIS1c") (pin "19") (pinfunction "MOUNT_19") (pintype "passive"))
    )
    (net (code "92") (name "unconnected-(DIS1c-MOUNT-Pad20)") (class "Default")
      (node (ref "DIS1c") (pin "20") (pinfunction "MOUNT_20") (pintype "passive"))
    )
    (net (code "93") (name "unconnected-(J2c-Pad2)") (class "Default")
      (node (ref "J2c") (pin "2") (pinfunction "2_2") (pintype "passive"))
    )
    (net (code "94") (name "unconnected-(J2c-Pad5)") (class "Default")
      (node (ref "J2c") (pin "5") (pinfunction "5_5") (pintype "passive"))
    )
    (net (code "95") (name "unconnected-(J3c-NC-Pad4)") (class "Default")
      (node (ref "J3c") (pin "4") (pinfunction "NC_4") (pintype "passive"))
    )
    (net (code "96") (name "unconnected-(J3c-SHIELD-Pad6)") (class "Default")
      (node (ref "J3c") (pin "6") (pinfunction "SHIELD_6") (pintype "passive"))
    )
    (net (code "97") (name "unconnected-(J3c-SHIELD-Pad7)") (class "Default")
      (node (ref "J3c") (pin "7") (pinfunction "SHIELD_7") (pintype "passive"))
    )
    (net (code "98") (name "unconnected-(J3c-SHIELD-Pad8)") (class "Default")
      (node (ref "J3c") (pin "8") (pinfunction "SHIELD_8") (pintype "passive"))
    )
    (net (code "99") (name "unconnected-(J3c-SHIELD-Pad9)") (class "Default")
      (node (ref "J3c") (pin "9") (pinfunction "SHIELD_9") (pintype "passive"))
    )
    (net (code "100") (name "unconnected-(U1c-JTDI{slash}TIM2CH1ETR(r){slash}PA15(r){slash}SPI1NSS(r)-Pad50)") (class "Default")
      (node (ref "U1c") (pin "50") (pinfunction "JTDI/TIM2CH1ETR(r)/PA15(r)/SPI1NSS(r)_50") (pintype "passive"))
    )
    (net (code "101") (name "unconnected-(U1c-PB13{slash}SPI2SCK{slash}USART3CTS{slash}TIM1CH1N-Pad34)") (class "Default")
      (node (ref "U1c") (pin "34") (pinfunction "PB13/SPI2SCK/USART3CTS/TIM1CH1N_34") (pintype "passive"))
    )
    (net (code "102") (name "unconnected-(U1c-PB14{slash}SPI2MISO{slash}USART3RTS{slash}TIM1CH2N-Pad35)") (class "Default")
      (node (ref "U1c") (pin "35") (pinfunction "PB14/SPI2MISO/USART3RTS/TIM1CH2N_35") (pintype "passive"))
    )
    (net (code "103") (name "unconnected-(U1c-PB15{slash}SPI2MOSI{slash}TIM1CH3N-Pad36)") (class "Default")
      (node (ref "U1c") (pin "36") (pinfunction "PB15/SPI2MOSI/TIM1CH3N_36") (pintype "passive"))
    )
    (net (code "104") (name "unconnected-(U1c-PC12{slash}UASRT3CK(r)-Pad53)") (class "Default")
      (node (ref "U1c") (pin "53") (pinfunction "PC12/UASRT3CK(r)_53") (pintype "passive"))
    )
    (net (code "105") (name "unconnected-(U1c-PC13{slash}TAMPER{slash}RTC-Pad2)") (class "Default")
      (node (ref "U1c") (pin "2") (pinfunction "PC13/TAMPER/RTC_2") (pintype "passive"))
    )
    (net (code "106") (name "unconnected-(U1c-PD2{slash}TIM3ETR-Pad54)") (class "Default")
      (node (ref "U1c") (pin "54") (pinfunction "PD2/TIM3ETR_54") (pintype "passive"))
    )
    (net (code "107") (name "unconnected-(U3c-B0-Pad18)") (class "Default")
      (node (ref "U3c") (pin "18") (pinfunction "B0_18") (pintype "passive"))
    )
    (net (code "108") (name "unconnected-(U3c-B1-Pad17)") (class "Default")
      (node (ref "U3c") (pin "17") (pinfunction "B1_17") (pintype "passive"))
    )
    (net (code "109") (name "unconnected-(U3c-B2-Pad16)") (class "Default")
      (node (ref "U3c") (pin "16") (pinfunction "B2_16") (pintype "passive"))
    )
    (net (code "110") (name "unconnected-(U3c-B3-Pad15)") (class "Default")
      (node (ref "U3c") (pin "15") (pinfunction "B3_15") (pintype "passive"))
    )
    (net (code "111") (name "unconnected-(U3c-B4-Pad14)") (class "Default")
      (node (ref "U3c") (pin "14") (pinfunction "B4_14") (pintype "passive"))
    )
  )
)
